# Oscillators.net
KiCad netlist of a schematic drawn in Altium Designer
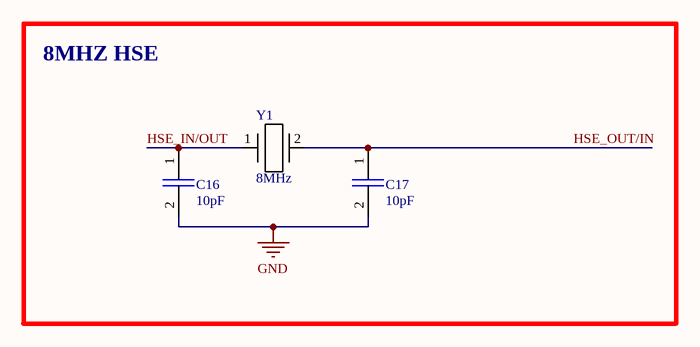
[diagram p0: Oscillators.SchDoc]

(export (version "E")
  (design (tool "Eeschema 10.0.6"))
  (components
    (comp (ref "C16")
      (value "10pF")
      (footprint "0603 Cap")
      (description "SMD 0603 (ceramic) capacitor")
      (fields
        (field (name "MANUFACTURER") "Murata")
        (field (name "MANUFACTURER PART NUMBER") "GRM21BR71C225KA12L")
      )
      (libsource (lib "Lib") (part "0603 Cap"))
    )
    (comp (ref "C17")
      (value "10pF")
      (footprint "0603 Cap")
      (description "SMD 0603 (ceramic) capacitor")
      (fields
        (field (name "MANUFACTURER") "Murata")
        (field (name "MANUFACTURER PART NUMBER") "GRM21BR71C225KA12L")
      )
      (libsource (lib "Lib") (part "0603 Cap"))
    )
    (comp (ref "Y1")
      (value "8MHz")
      (footprint "ABM3 2PIN SMD")
      (description "XTAL schematic. Footprint available for many packages")
      (fields (field (name "Comment") "XTAL"))
      (libsource (lib "Lib") (part "XTAL"))
    )
  )
  (nets
    (net (code "1") (name "/HSE_IN{slash}OUT") (class "Default")
      (node (ref "C16") (pin "1") (pinfunction "11_1") (pintype "passive"))
      (node (ref "Y1") (pin "1") (pinfunction "29_1") (pintype "passive"))
    )
    (net (code "2") (name "/HSE_OUT{slash}IN") (class "Default")
      (node (ref "C17") (pin "1") (pinfunction "11_1") (pintype "passive"))
      (node (ref "Y1") (pin "2") (pinfunction "28_2") (pintype "passive"))
    )
    (net (code "3") (name "GND") (class "Default")
      (node (ref "C16") (pin "2") (pinfunction "12_2") (pintype "passive"))
      (node (ref "C17") (pin "2") (pinfunction "12_2") (pintype "passive"))
    )
  )
)
